# TopLevel.net
KiCad netlist of a schematic drawn in Altium Designer
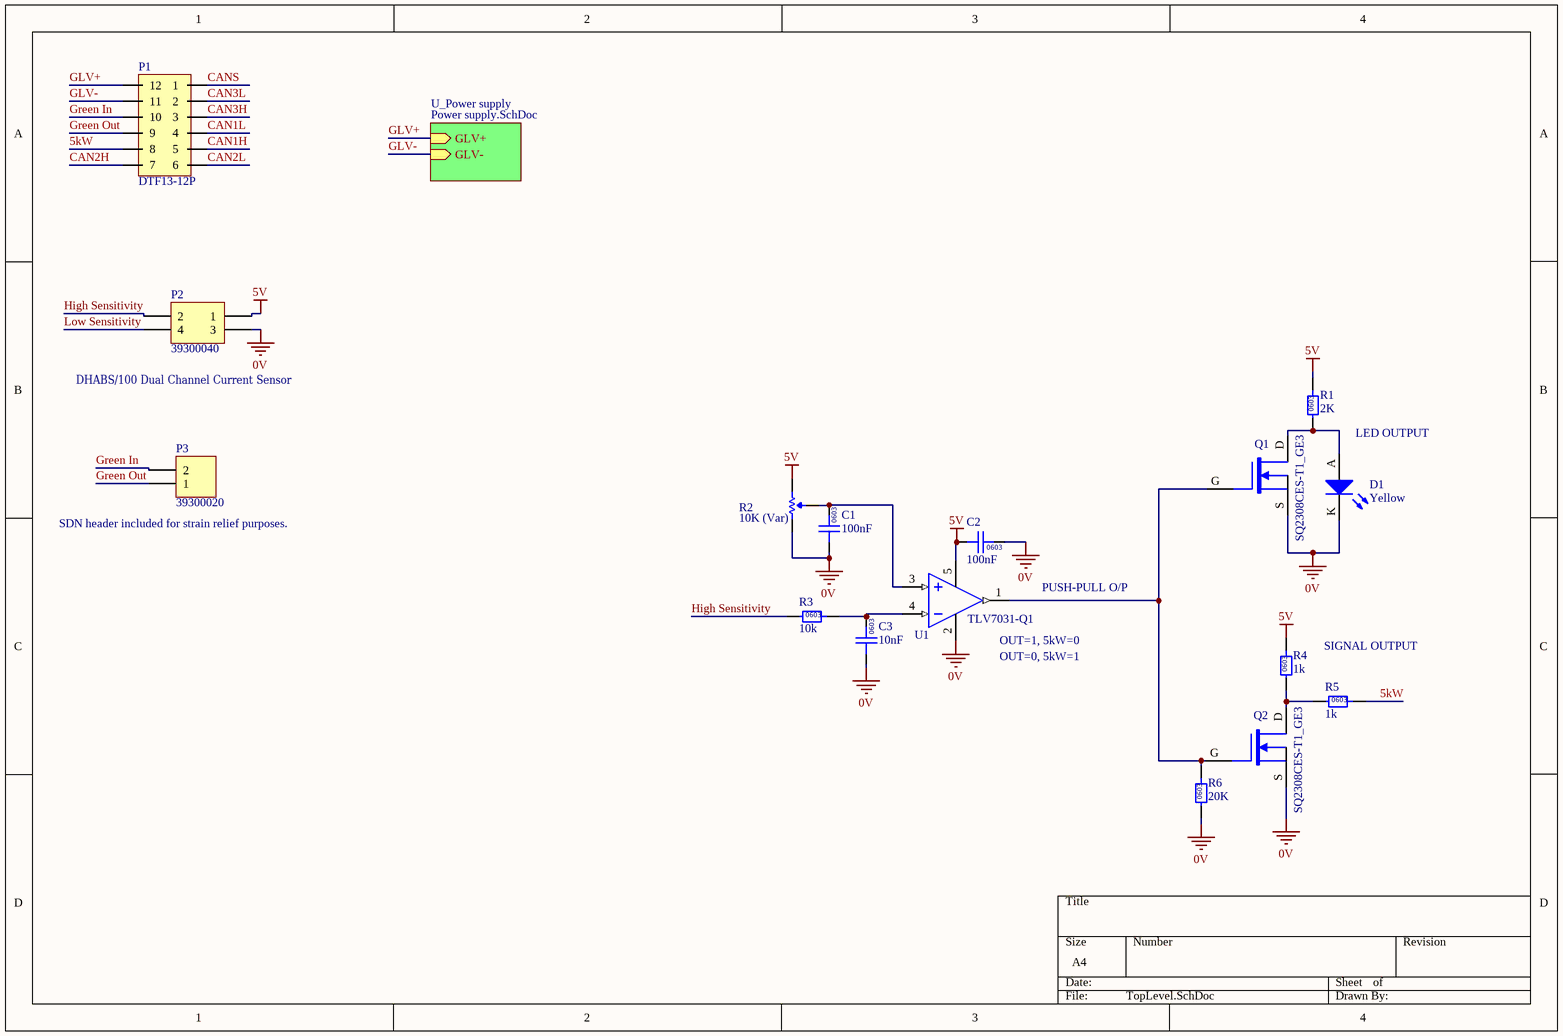
[diagram p0: TopLevel.SchDoc]

(export (version "E")
  (design (tool "Eeschema 10.0.6"))
  (components
    (comp (ref "C1")
      (value "100nF")
      (footprint "0603")
      (fields
        (field (name "PART NUMBER") "GCM188L81H104KA57D")
        (field (name "MANUFACTURER") "muRata")
        (field (name "TOLERANCE") "±10%")
      )
      (libsource (lib "ts_standard_library") (part "Capacitor 0603"))
    )
    (comp (ref "C2")
      (value "100nF")
      (footprint "0603")
      (fields
        (field (name "PART NUMBER") "GCM188L81H104KA57D")
        (field (name "MANUFACTURER") "muRata")
        (field (name "TOLERANCE") "±10%")
      )
      (libsource (lib "ts_standard_library") (part "Capacitor 0603"))
    )
    (comp (ref "C3")
      (value "10nF")
      (footprint "0603")
      (fields
        (field (name "PART NUMBER") "GCM188L81H103KA03D")
        (field (name "MANUFACTURER") "muRata")
        (field (name "TOLERANCE") "±10%")
      )
      (libsource (lib "ts_standard_library") (part "Capacitor 0603"))
    )
    (comp (ref "D1")
      (value "Yellow")
      (footprint "0805 LED")
      (description "Yellow LED Indication - Discrete 1.75V 0805 (2012 Metric)")
      (fields (field (name "PART NUMBER") "SML-211YTT86") (field (name "MANUFACTURER") "ROHM Semiconductor"))
      (libsource (lib "ts_standard_library") (part "LED"))
    )
    (comp (ref "P1")
      (value "DTF13-12P")
      (footprint "DTF13-12P")
      (fields (field (name "DIGIKEY PART NUMBER") "1734-1861-ND") (field (name "CONTACT") "Copper Alloy"))
      (libsource (lib "ts_standard_connectors") (part "DT13-12P"))
    )
    (comp (ref "P2")
      (value "39300040")
      (footprint "39300040")
      (fields (field (name "DIGIKEY PART NUMBER") "WM21352-ND") (field (name "CONTACT") "Tin"))
      (libsource (lib "ts_standard_connectors") (part "4"))
    )
    (comp (ref "P3")
      (value "39300020")
      (footprint "39300020")
      (fields (field (name "DIGIKEY PART NUMBER") "WM21351-ND") (field (name "CONTACT") "Tin"))
      (libsource (lib "ts_standard_connectors") (part "2"))
    )
    (comp (ref "Q1")
      (value "SQ2308CES-T1_GE3")
      (footprint "VSHY SOT-23-3")
      (description "MOSFET N-CH 60V 2.3A SOT23")
      (fields
        (field (name "MANUFACTURER") "Vishay Siliconix")
        (field (name "DIGIKEY PART NUMBER") "SQ2308CES-T1_GE3CT-ND")
        (field (name "PUBLISHER") "Altium Limited")
      )
      (libsource (lib "ts_standard_library") (part "MOSFET-N"))
    )
    (comp (ref "Q2")
      (value "SQ2308CES-T1_GE3")
      (footprint "VSHY SOT-23-3")
      (description "MOSFET N-CH 60V 2.3A SOT23")
      (fields
        (field (name "MANUFACTURER") "Vishay Siliconix")
        (field (name "DIGIKEY PART NUMBER") "SQ2308CES-T1_GE3CT-ND")
        (field (name "PUBLISHER") "Altium Limited")
      )
      (libsource (lib "ts_standard_library") (part "MOSFET-N"))
    )
    (comp (ref "R1")
      (value "2K")
      (footprint "0603")
      (fields
        (field (name "PART NUMBER") "RC0603FR-072KL")
        (field (name "MANUFACTURER") "YAGEO")
        (field (name "TOLERANCE") "0.01")
      )
      (libsource (lib "ts_standard_library") (part "Resistor 0603"))
    )
    (comp (ref "R2")
      (value "10K (Var)")
      (footprint "B 3296")
      (fields
        (field (name "PART NUMBER") "3296W-1-103LF")
        (field (name "MANUFACTURER") "Bournes Inc")
        (field (name "TOLERANCE") "0.1")
      )
      (libsource (lib "ts_standard_library") (part "Resistor (Potentiometer)"))
    )
    (comp (ref "R3")
      (value "10k")
      (footprint "0603")
      (fields
        (field (name "PART NUMBER") "RC0603FR-0710KL")
        (field (name "MANUFACTURER") "YAGEO")
        (field (name "TOLERANCE") "0.01")
      )
      (libsource (lib "ts_standard_library") (part "Resistor 0603"))
    )
    (comp (ref "R4")
      (value "1k")
      (footprint "0603")
      (fields
        (field (name "PART NUMBER") "RC0603FR-071KL")
        (field (name "MANUFACTURER") "YAGEO")
        (field (name "TOLERANCE") "0.01")
      )
      (libsource (lib "ts_standard_library") (part "Resistor 0603"))
    )
    (comp (ref "R5")
      (value "1k")
      (footprint "0603")
      (fields
        (field (name "PART NUMBER") "RC0603FR-071KL")
        (field (name "MANUFACTURER") "YAGEO")
        (field (name "TOLERANCE") "0.01")
      )
      (libsource (lib "ts_standard_library") (part "Resistor 0603"))
    )
    (comp (ref "R6")
      (value "20K")
      (footprint "0603")
      (fields
        (field (name "PART NUMBER") "RC0603FR-0720KL")
        (field (name "MANUFACTURER") "YAGEO")
        (field (name "TOLERANCE") "0.01")
      )
      (libsource (lib "ts_standard_library") (part "Resistor 0603"))
    )
    (comp (ref "U1")
      (value "TLV7031-Q1")
      (footprint "TI SOT-23-5")
      (fields
        (field (name "MANUFACTURER") "Texas Instruments")
        (field (name "DIGIKEY PART NUMBER") "296-TLV7031QDBVRQ1CT-ND")
      )
      (libsource (lib "ts_standard_library") (part "TLV7031-Q1"))
    )
  )
  (nets
    (net (code "1") (name "/5kW") (class "Default")
      (node (ref "P1") (pin "8") (pinfunction "8_8") (pintype "passive"))
      (node (ref "R5") (pin "2") (pinfunction "2_2") (pintype "passive"))
    )
    (net (code "2") (name "/CAN1H") (class "Default")
      (node (ref "P1") (pin "5") (pinfunction "5_5") (pintype "passive"))
    )
    (net (code "3") (name "/CAN1L") (class "Default")
      (node (ref "P1") (pin "4") (pinfunction "4_4") (pintype "passive"))
    )
    (net (code "4") (name "/CAN2H") (class "Default")
      (node (ref "P1") (pin "7") (pinfunction "7_7") (pintype "passive"))
    )
    (net (code "5") (name "/CAN2L") (class "Default")
      (node (ref "P1") (pin "6") (pinfunction "6_6") (pintype "passive"))
    )
    (net (code "6") (name "/CAN3H") (class "Default")
      (node (ref "P1") (pin "3") (pinfunction "3_3") (pintype "passive"))
    )
    (net (code "7") (name "/CAN3L") (class "Default")
      (node (ref "P1") (pin "2") (pinfunction "2_2") (pintype "passive"))
    )
    (net (code "8") (name "/CANS") (class "Default")
      (node (ref "P1") (pin "1") (pinfunction "1_1") (pintype "passive"))
    )
    (net (code "9") (name "/GLV+") (class "Default")
      (node (ref "P1") (pin "12") (pinfunction "12_12") (pintype "passive"))
    )
    (net (code "10") (name "/GLV-") (class "Default")
      (node (ref "P1") (pin "11") (pinfunction "11_11") (pintype "passive"))
    )
    (net (code "11") (name "/Green In") (class "Default")
      (node (ref "P1") (pin "10") (pinfunction "10_10") (pintype "passive"))
      (node (ref "P3") (pin "2") (pinfunction "2_2") (pintype "passive"))
    )
    (net (code "12") (name "/Green Out") (class "Default")
      (node (ref "P1") (pin "9") (pinfunction "9_9") (pintype "passive"))
      (node (ref "P3") (pin "1") (pinfunction "1_1") (pintype "passive"))
    )
    (net (code "13") (name "/High Sensitivity") (class "Default")
      (node (ref "P2") (pin "2") (pinfunction "2_2") (pintype "passive"))
      (node (ref "R3") (pin "1") (pinfunction "1_1") (pintype "passive"))
    )
    (net (code "14") (name "/Low Sensitivity") (class "Default")
      (node (ref "P2") (pin "4") (pinfunction "4_4") (pintype "passive"))
    )
    (net (code "15") (name "0V") (class "Default")
      (node (ref "C1") (pin "1") (pinfunction "1_1") (pintype "passive"))
      (node (ref "C2") (pin "2") (pinfunction "2_2") (pintype "passive"))
      (node (ref "C3") (pin "1") (pinfunction "1_1") (pintype "passive"))
      (node (ref "D1") (pin "K") (pinfunction "K_K") (pintype "passive"))
      (node (ref "P2") (pin "3") (pinfunction "3_3") (pintype "passive"))
      (node (ref "Q1") (pin "S") (pinfunction "S_S") (pintype "passive"))
      (node (ref "Q2") (pin "S") (pinfunction "S_S") (pintype "passive"))
      (node (ref "R2") (pin "3") (pinfunction "CW_3") (pintype "passive"))
      (node (ref "R6") (pin "1") (pinfunction "1_1") (pintype "passive"))
      (node (ref "U1") (pin "2") (pinfunction "V-_2") (pintype "power_in"))
    )
    (net (code "16") (name "5V") (class "Default")
      (node (ref "C2") (pin "1") (pinfunction "1_1") (pintype "passive"))
      (node (ref "P2") (pin "1") (pinfunction "1_1") (pintype "passive"))
      (node (ref "R1") (pin "2") (pinfunction "2_2") (pintype "passive"))
      (node (ref "R2") (pin "1") (pinfunction "CCW_1") (pintype "passive"))
      (node (ref "R4") (pin "2") (pinfunction "2_2") (pintype "passive"))
      (node (ref "U1") (pin "5") (pinfunction "Vcc_5") (pintype "power_in"))
    )
    (net (code "17") (name "Net-(D1-PadA)") (class "Default")
      (node (ref "D1") (pin "A") (pinfunction "A_A") (pintype "passive"))
      (node (ref "Q1") (pin "D") (pinfunction "D_D") (pintype "passive"))
      (node (ref "R1") (pin "1") (pinfunction "1_1") (pintype "passive"))
    )
    (net (code "18") (name "Net-(Q2-PadD)") (class "Default")
      (node (ref "Q2") (pin "D") (pinfunction "D_D") (pintype "passive"))
      (node (ref "R4") (pin "1") (pinfunction "1_1") (pintype "passive"))
      (node (ref "R5") (pin "1") (pinfunction "1_1") (pintype "passive"))
    )
    (net (code "19") (name "Net-(R2-Wiper)") (class "Default")
      (node (ref "C1") (pin "2") (pinfunction "2_2") (pintype "passive"))
      (node (ref "R2") (pin "2") (pinfunction "Wiper_2") (pintype "passive"))
      (node (ref "U1") (pin "3") (pinfunction "IN+_3") (pintype "input"))
    )
    (net (code "20") (name "Net-(U1-IN-)") (class "Default")
      (node (ref "C3") (pin "2") (pinfunction "2_2") (pintype "passive"))
      (node (ref "R3") (pin "2") (pinfunction "2_2") (pintype "passive"))
      (node (ref "U1") (pin "4") (pinfunction "IN-_4") (pintype "input"))
    )
    (net (code "21") (name "Net-(U1-OUT)") (class "Default")
      (node (ref "Q1") (pin "G") (pinfunction "G_G") (pintype "passive"))
      (node (ref "Q2") (pin "G") (pinfunction "G_G") (pintype "passive"))
      (node (ref "R6") (pin "2") (pinfunction "2_2") (pintype "passive"))
      (node (ref "U1") (pin "1") (pinfunction "OUT_1") (pintype "output"))
    )
  )
)
